# master.net
KiCad netlist of a schematic drawn in Altium Designer
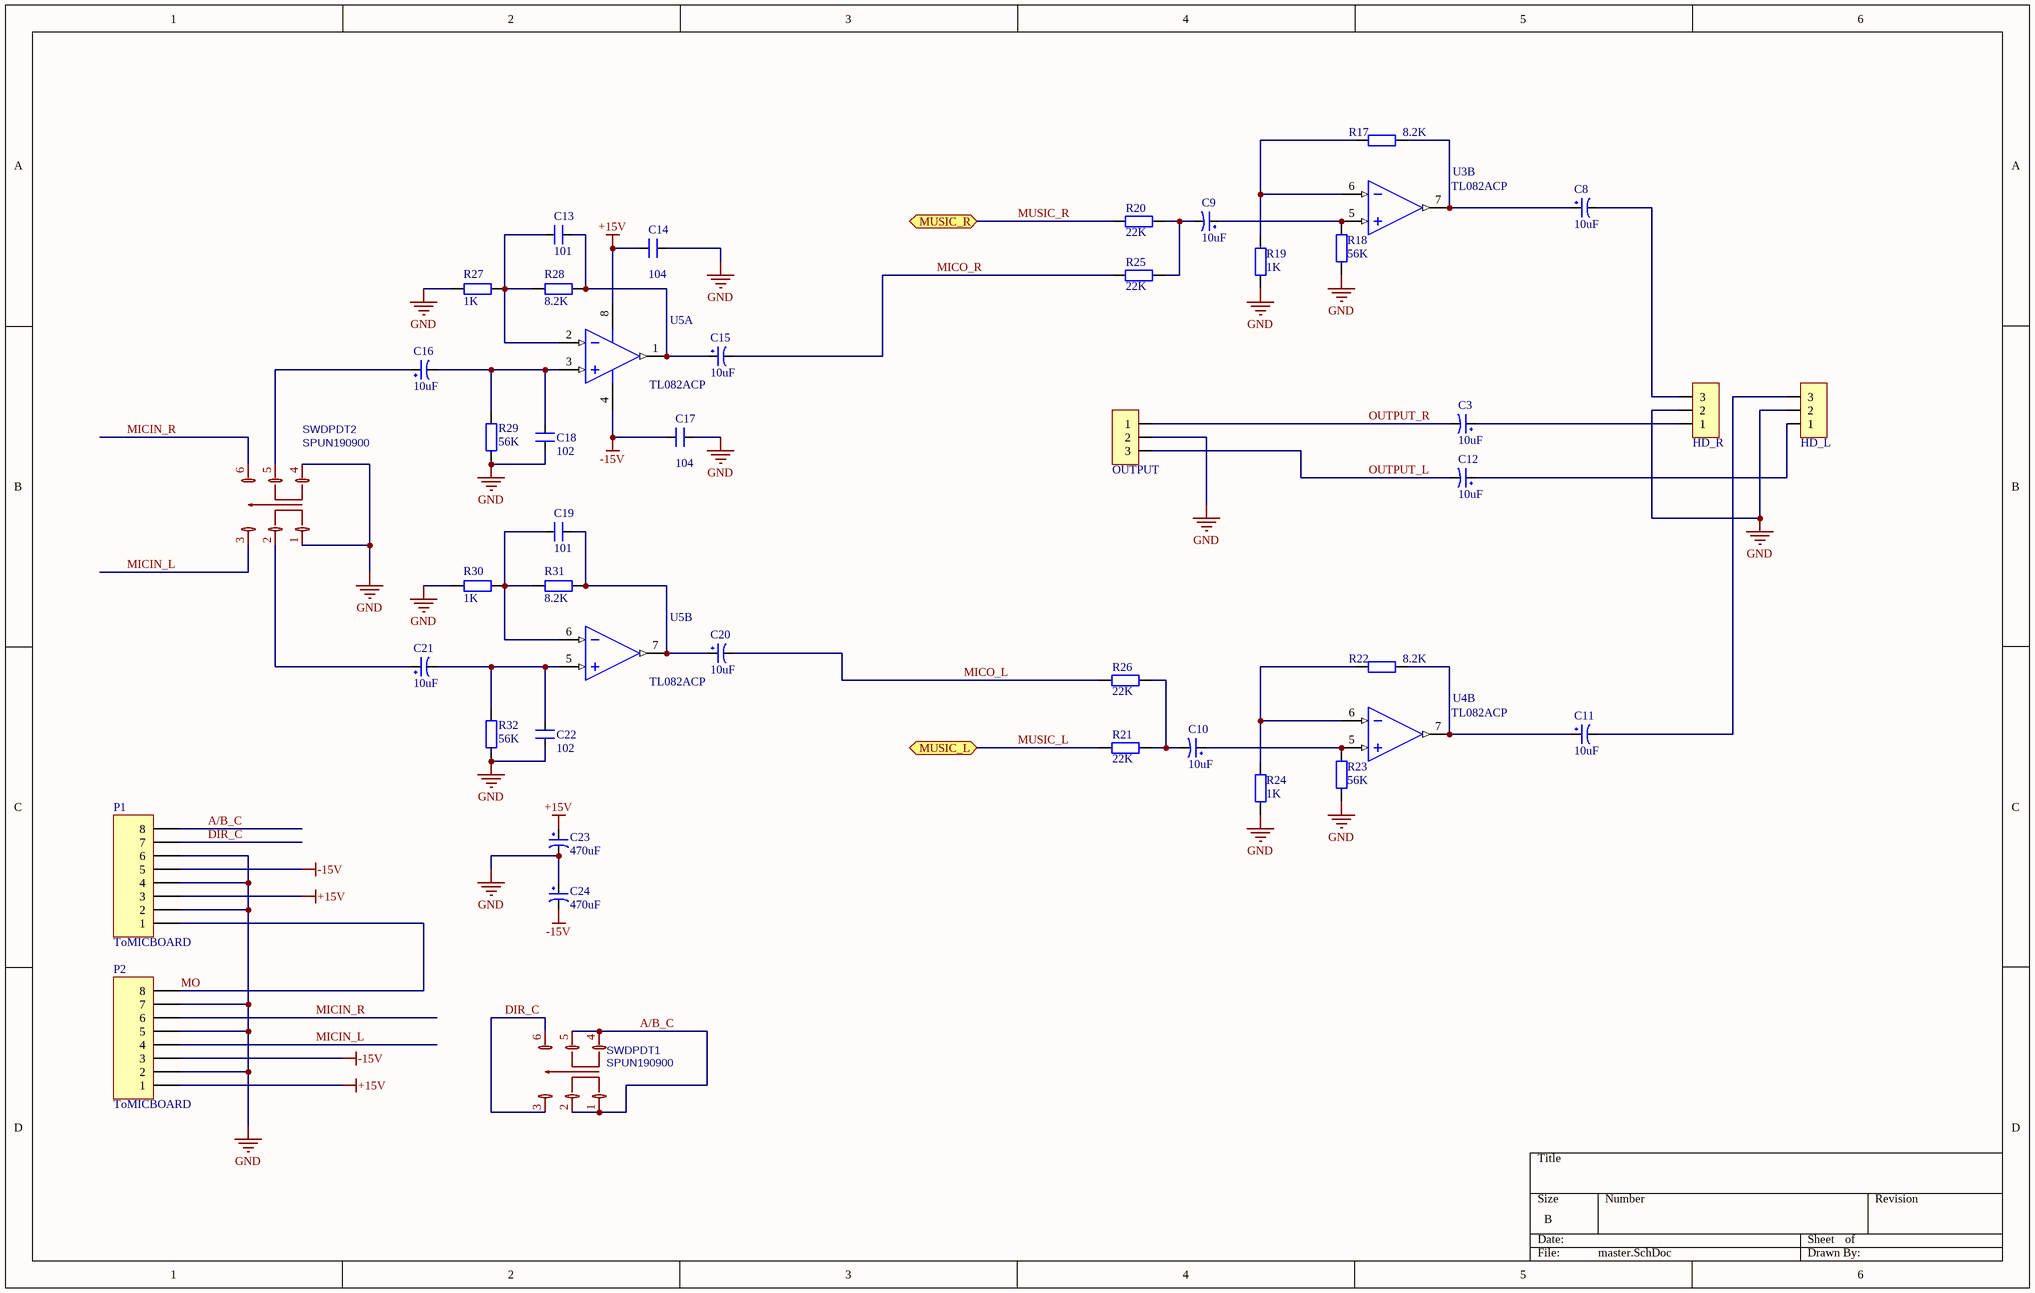
[diagram p0: master.SchDoc]

(export (version "E")
  (design (tool "Eeschema 10.0.6"))
  (components
    (comp (ref "C3")
      (value "10uF")
      (footprint "CAP5x12")
      (description "TU_HOA_4.7uF_100V_MH")
      (libsource (lib "MH_DA_THU_VIEN_16122016") (part "TU_HOA_4.7uF_100V_MH"))
    )
    (comp (ref "C8")
      (value "10uF")
      (footprint "CAP5x12")
      (description "TU_HOA_4.7uF_100V_MH")
      (libsource (lib "MH_DA_THU_VIEN_16122016") (part "TU_HOA_4.7uF_100V_MH"))
    )
    (comp (ref "C9")
      (value "10uF")
      (footprint "CAP5x12")
      (description "TU_HOA_4.7uF_100V_MH")
      (libsource (lib "MH_DA_THU_VIEN_16122016") (part "TU_HOA_4.7uF_100V_MH"))
    )
    (comp (ref "C10")
      (value "10uF")
      (footprint "CAP5x12")
      (description "TU_HOA_4.7uF_100V_MH")
      (libsource (lib "MH_DA_THU_VIEN_16122016") (part "TU_HOA_4.7uF_100V_MH"))
    )
    (comp (ref "C11")
      (value "10uF")
      (footprint "CAP5x12")
      (description "TU_HOA_4.7uF_100V_MH")
      (libsource (lib "MH_DA_THU_VIEN_16122016") (part "TU_HOA_4.7uF_100V_MH"))
    )
    (comp (ref "C12")
      (value "10uF")
      (footprint "CAP5x12")
      (description "TU_HOA_4.7uF_100V_MH")
      (libsource (lib "MH_DA_THU_VIEN_16122016") (part "TU_HOA_4.7uF_100V_MH"))
    )
    (comp (ref "C13")
      (value "101")
      (footprint "TU_GOM(104-->105pF)")
      (libsource (lib "MH_DA_THU_VIEN_16122016") (part "TU_GOM(104 ={gt} 105pF)_MH"))
    )
    (comp (ref "C14")
      (value "104")
      (footprint "TU_GOM(104-->105pF)")
      (libsource (lib "MH_DA_THU_VIEN_16122016") (part "TU_MICA_ 104 100V(2A104J)_MH"))
    )
    (comp (ref "C15")
      (value "10uF")
      (footprint "CAP5x12")
      (description "TU_HOA_4.7uF_100V_MH")
      (libsource (lib "MH_DA_THU_VIEN_16122016") (part "TU_HOA_4.7uF_100V_MH"))
    )
    (comp (ref "C16") (value "10uF") (footprint "CAP5x12") (libsource (lib "") (part "TU_HOA_10uF_16V_MH_1")))
    (comp (ref "C17")
      (value "104")
      (footprint "TU_GOM(104-->105pF)")
      (libsource (lib "MH_DA_THU_VIEN_16122016") (part "TU_MICA_ 104 100V(2A104J)_MH"))
    )
    (comp (ref "C18")
      (value "102")
      (footprint "TU_GOM(104-->105pF)")
      (libsource (lib "MH_DA_THU_VIEN_16122016") (part "TU_GOM(104 ={gt} 105pF)_MH"))
    )
    (comp (ref "C19")
      (value "101")
      (footprint "TU_GOM(104-->105pF)")
      (libsource (lib "MH_DA_THU_VIEN_16122016") (part "TU_GOM(104 ={gt} 105pF)_MH"))
    )
    (comp (ref "C20")
      (value "10uF")
      (footprint "CAP5x12")
      (description "TU_HOA_4.7uF_100V_MH")
      (libsource (lib "MH_DA_THU_VIEN_16122016") (part "TU_HOA_4.7uF_100V_MH"))
    )
    (comp (ref "C21") (value "10uF") (footprint "CAP5x12") (libsource (lib "") (part "TU_HOA_10uF_16V_MH_1")))
    (comp (ref "C22")
      (value "102")
      (footprint "TU_GOM(104-->105pF)")
      (libsource (lib "MH_DA_THU_VIEN_16122016") (part "TU_GOM(104 ={gt} 105pF)_MH"))
    )
    (comp (ref "C23")
      (value "470uF")
      (footprint "TU_HOA(100uF/35V - 470uF/16V)")
      (description "10uF")
      (libsource (lib "MH_DA_THU_VIEN_16122016") (part "TU_HOA_10uF_16V_MH"))
    )
    (comp (ref "C24")
      (value "470uF")
      (footprint "TU_HOA(100uF/35V - 470uF/16V)")
      (description "10uF")
      (libsource (lib "MH_DA_THU_VIEN_16122016") (part "TU_HOA_10uF_16V_MH"))
    )
    (comp (ref "HD_L")
      (value "Header 3_MH")
      (footprint "HEADER 3")
      (description "Header 3P XH2.54 thẳng")
      (libsource (lib "MH_DA_THU_VIEN_16122016") (part "Header 3_MH"))
    )
    (comp (ref "HD_R")
      (value "Header 3_MH")
      (footprint "HEADER 3")
      (description "Header 3P XH2.54 thẳng")
      (libsource (lib "MH_DA_THU_VIEN_16122016") (part "Header 3_MH"))
    )
    (comp (ref "OUTPUT")
      (value "Header 3_MH")
      (footprint "HEADER 3")
      (description "Header 3P XH2.54 thẳng")
      (libsource (lib "") (part "Header 3_MH_1"))
    )
    (comp (ref "P1")
      (value "ToMICBOARD")
      (footprint "HEADER 8")
      (description "Header, 8-Pin")
      (fields (field (name "PUBLISHER") "Altium Limited"))
      (libsource (lib "Miscellaneous Connectors") (part "Header 8"))
    )
    (comp (ref "P2")
      (value "ToMICBOARD")
      (footprint "HEADER 8")
      (description "Header, 8-Pin")
      (fields (field (name "PUBLISHER") "Altium Limited"))
      (libsource (lib "Miscellaneous Connectors") (part "Header 8"))
    )
    (comp (ref "R17")
      (value "8.2K")
      (footprint "TRO_VACH_ 1/4W")
      (description "Resistor")
      (fields (field (name "PUBLISHER") "Altium Limited"))
      (libsource (lib "") (part "TRO_VACH_1/2W_MH_2"))
    )
    (comp (ref "R18")
      (value "56K")
      (footprint "TRO_VACH_ 1/4W")
      (description "Resistor")
      (fields (field (name "PUBLISHER") "Altium Limited"))
      (libsource (lib "MH_DA_THU_VIEN_16122016") (part "TRO_VACH_1/2W_MH"))
    )
    (comp (ref "R19")
      (value "1K")
      (footprint "TRO_VACH_ 1/4W")
      (description "Resistor")
      (fields (field (name "PUBLISHER") "Altium Limited"))
      (libsource (lib "MH_DA_THU_VIEN_16122016") (part "TRO_VACH_1/2W_MH"))
    )
    (comp (ref "R20")
      (value "22K")
      (footprint "TRO_VACH_ 1/4W")
      (description "Resistor")
      (fields (field (name "PUBLISHER") "Altium Limited"))
      (libsource (lib "") (part "TRO_VACH_1/2W_MH_1"))
    )
    (comp (ref "R21")
      (value "22K")
      (footprint "TRO_VACH_ 1/4W")
      (description "Resistor")
      (fields (field (name "PUBLISHER") "Altium Limited"))
      (libsource (lib "") (part "TRO_VACH_1/2W_MH_1"))
    )
    (comp (ref "R22")
      (value "8.2K")
      (footprint "TRO_VACH_ 1/4W")
      (description "Resistor")
      (fields (field (name "PUBLISHER") "Altium Limited"))
      (libsource (lib "") (part "TRO_VACH_1/2W_MH_2"))
    )
    (comp (ref "R23")
      (value "56K")
      (footprint "TRO_VACH_ 1/4W")
      (description "Resistor")
      (fields (field (name "PUBLISHER") "Altium Limited"))
      (libsource (lib "MH_DA_THU_VIEN_16122016") (part "TRO_VACH_1/2W_MH"))
    )
    (comp (ref "R24")
      (value "1K")
      (footprint "TRO_VACH_ 1/4W")
      (description "Resistor")
      (fields (field (name "PUBLISHER") "Altium Limited"))
      (libsource (lib "MH_DA_THU_VIEN_16122016") (part "TRO_VACH_1/2W_MH"))
    )
    (comp (ref "R25")
      (value "22K")
      (footprint "TRO_VACH_ 1/4W")
      (description "Resistor")
      (fields (field (name "PUBLISHER") "Altium Limited"))
      (libsource (lib "") (part "TRO_VACH_1/2W_MH_1"))
    )
    (comp (ref "R26")
      (value "22K")
      (footprint "TRO_VACH_ 1/4W")
      (description "Resistor")
      (fields (field (name "PUBLISHER") "Altium Limited"))
      (libsource (lib "") (part "TRO_VACH_1/2W_MH_1"))
    )
    (comp (ref "R27")
      (value "1K")
      (footprint "TRO_VACH_ 1/4W")
      (libsource (lib "MH_DA_THU_VIEN_16122016") (part "TRO_VACH_1/4W_MH"))
    )
    (comp (ref "R28")
      (value "8.2K")
      (footprint "TRO_VACH_ 1/4W")
      (libsource (lib "MH_DA_THU_VIEN_16122016") (part "TRO_VACH_1/4W_MH"))
    )
    (comp (ref "R29")
      (value "56K")
      (footprint "TRO_VACH_ 1/4W")
      (libsource (lib "MH_DA_THU_VIEN_16122016") (part "TRO_VACH_1/4W_MH"))
    )
    (comp (ref "R30")
      (value "1K")
      (footprint "TRO_VACH_ 1/4W")
      (libsource (lib "MH_DA_THU_VIEN_16122016") (part "TRO_VACH_1/4W_MH"))
    )
    (comp (ref "R31")
      (value "8.2K")
      (footprint "TRO_VACH_ 1/4W")
      (libsource (lib "MH_DA_THU_VIEN_16122016") (part "TRO_VACH_1/4W_MH"))
    )
    (comp (ref "R32")
      (value "56K")
      (footprint "TRO_VACH_ 1/4W")
      (libsource (lib "MH_DA_THU_VIEN_16122016") (part "TRO_VACH_1/4W_MH"))
    )
    (comp (ref "SWDPDT1")
      (value "SPUN190900")
      (footprint "SW-DIP-P42X10")
      (fields (field (name "BOM_SUPPLIER PART") "C278339") (field (name "CONTRIBUTOR") "LCSC"))
      (libsource (lib "Schlib1") (part "SPUN190900"))
    )
    (comp (ref "SWDPDT2")
      (value "SPUN190900")
      (footprint "SW-DIP-P42X10")
      (fields (field (name "BOM_SUPPLIER PART") "C278339") (field (name "CONTRIBUTOR") "LCSC"))
      (libsource (lib "Schlib1") (part "SPUN190900"))
    )
    (comp (ref "U3")
      (value "TL082ACP")
      (footprint "DIP8")
      (description "JFET-Input Operational Amplifier")
      (fields (field (name "PUBLISHER") "Altium Limited"))
      (libsource (lib "Schlib1") (part "TL082ACP"))
    )
    (comp (ref "U4")
      (value "TL082ACP")
      (footprint "DIP8")
      (description "JFET-Input Operational Amplifier")
      (fields (field (name "PUBLISHER") "Altium Limited"))
      (libsource (lib "Schlib1") (part "TL082ACP"))
    )
    (comp (ref "U5")
      (value "TL082ACP")
      (footprint "DIP8")
      (description "JFET-Input Operational Amplifier")
      (fields (field (name "PUBLISHER") "Altium Limited"))
      (libsource (lib "Schlib1") (part "TL082ACP"))
    )
  )
  (nets
    (net (code "1") (name "+15V") (class "Default")
      (node (ref "C14") (pin "1") (pinfunction "1_1") (pintype "passive"))
      (node (ref "C23") (pin "1") (pinfunction "1_1") (pintype "passive"))
      (node (ref "P1") (pin "3") (pinfunction "3_3") (pintype "passive"))
      (node (ref "P2") (pin "1") (pinfunction "1_1") (pintype "passive"))
      (node (ref "U5") (pin "8") (pinfunction "V+_8") (pintype "power_in"))
    )
    (net (code "2") (name "-15V") (class "Default")
      (node (ref "C17") (pin "1") (pinfunction "1_1") (pintype "passive"))
      (node (ref "C24") (pin "2") (pinfunction "2_2") (pintype "passive"))
      (node (ref "P1") (pin "5") (pinfunction "5_5") (pintype "passive"))
      (node (ref "P2") (pin "3") (pinfunction "3_3") (pintype "passive"))
      (node (ref "U5") (pin "4") (pinfunction "V-_4") (pintype "power_in"))
    )
    (net (code "3") (name "/A{slash}B_C") (class "Default")
      (node (ref "P1") (pin "8") (pinfunction "8_8") (pintype "passive"))
      (node (ref "SWDPDT1") (pin "1") (pinfunction "1_1") (pintype "passive"))
      (node (ref "SWDPDT1") (pin "2") (pinfunction "2_2") (pintype "passive"))
      (node (ref "SWDPDT1") (pin "4") (pinfunction "4_4") (pintype "passive"))
      (node (ref "SWDPDT1") (pin "5") (pinfunction "5_5") (pintype "passive"))
    )
    (net (code "4") (name "/DIR_C") (class "Default")
      (node (ref "P1") (pin "7") (pinfunction "7_7") (pintype "passive"))
      (node (ref "SWDPDT1") (pin "3") (pinfunction "3_3") (pintype "passive"))
      (node (ref "SWDPDT1") (pin "6") (pinfunction "6_6") (pintype "passive"))
    )
    (net (code "5") (name "/MICIN_L") (class "Default")
      (node (ref "P2") (pin "4") (pinfunction "4_4") (pintype "passive"))
      (node (ref "SWDPDT2") (pin "3") (pinfunction "3_3") (pintype "passive"))
    )
    (net (code "6") (name "/MICIN_R") (class "Default")
      (node (ref "P2") (pin "6") (pinfunction "6_6") (pintype "passive"))
      (node (ref "SWDPDT2") (pin "6") (pinfunction "6_6") (pintype "passive"))
    )
    (net (code "7") (name "/MICO_L") (class "Default")
      (node (ref "C20") (pin "2") (pinfunction "2_2") (pintype "passive"))
      (node (ref "R26") (pin "1") (pinfunction "1_1") (pintype "passive"))
    )
    (net (code "8") (name "/MICO_R") (class "Default")
      (node (ref "C15") (pin "2") (pinfunction "2_2") (pintype "passive"))
      (node (ref "R25") (pin "1") (pinfunction "1_1") (pintype "passive"))
    )
    (net (code "9") (name "/MO") (class "Default")
      (node (ref "P1") (pin "1") (pinfunction "1_1") (pintype "passive"))
      (node (ref "P2") (pin "8") (pinfunction "8_8") (pintype "passive"))
    )
    (net (code "10") (name "/MUSIC_L") (class "Default")
      (node (ref "R21") (pin "1") (pinfunction "1_1") (pintype "passive"))
    )
    (net (code "11") (name "/MUSIC_R") (class "Default")
      (node (ref "R20") (pin "1") (pinfunction "1_1") (pintype "passive"))
    )
    (net (code "12") (name "/OUTPUT_L") (class "Default")
      (node (ref "C12") (pin "2") (pinfunction "2_2") (pintype "passive"))
      (node (ref "OUTPUT") (pin "3") (pinfunction "3_3") (pintype "passive"))
    )
    (net (code "13") (name "/OUTPUT_R") (class "Default")
      (node (ref "C3") (pin "2") (pinfunction "2_2") (pintype "passive"))
      (node (ref "OUTPUT") (pin "1") (pinfunction "1_1") (pintype "passive"))
    )
    (net (code "14") (name "GND") (class "Default")
      (node (ref "C14") (pin "2") (pinfunction "2_2") (pintype "passive"))
      (node (ref "C17") (pin "2") (pinfunction "2_2") (pintype "passive"))
      (node (ref "C18") (pin "1") (pinfunction "1_1") (pintype "passive"))
      (node (ref "C22") (pin "1") (pinfunction "1_1") (pintype "passive"))
      (node (ref "C23") (pin "2") (pinfunction "2_2") (pintype "passive"))
      (node (ref "C24") (pin "1") (pinfunction "1_1") (pintype "passive"))
      (node (ref "HD_L") (pin "2") (pinfunction "2_2") (pintype "passive"))
      (node (ref "HD_R") (pin "2") (pinfunction "2_2") (pintype "passive"))
      (node (ref "OUTPUT") (pin "2") (pinfunction "2_2") (pintype "passive"))
      (node (ref "P1") (pin "2") (pinfunction "2_2") (pintype "passive"))
      (node (ref "P1") (pin "4") (pinfunction "4_4") (pintype "passive"))
      (node (ref "P1") (pin "6") (pinfunction "6_6") (pintype "passive"))
      (node (ref "P2") (pin "2") (pinfunction "2_2") (pintype "passive"))
      (node (ref "P2") (pin "5") (pinfunction "5_5") (pintype "passive"))
      (node (ref "P2") (pin "7") (pinfunction "7_7") (pintype "passive"))
      (node (ref "R18") (pin "2") (pinfunction "2_2") (pintype "passive"))
      (node (ref "R19") (pin "2") (pinfunction "2_2") (pintype "passive"))
      (node (ref "R23") (pin "2") (pinfunction "2_2") (pintype "passive"))
      (node (ref "R24") (pin "2") (pinfunction "2_2") (pintype "passive"))
      (node (ref "R27") (pin "1") (pinfunction "1_1") (pintype "passive"))
      (node (ref "R29") (pin "1") (pinfunction "1_1") (pintype "passive"))
      (node (ref "R30") (pin "1") (pinfunction "1_1") (pintype "passive"))
      (node (ref "R32") (pin "1") (pinfunction "1_1") (pintype "passive"))
      (node (ref "SWDPDT2") (pin "1") (pinfunction "1_1") (pintype "passive"))
      (node (ref "SWDPDT2") (pin "4") (pinfunction "4_4") (pintype "passive"))
    )
    (net (code "15") (name "Net-(C3-Pad1)") (class "Default")
      (node (ref "C3") (pin "1") (pinfunction "1_1") (pintype "passive"))
      (node (ref "HD_R") (pin "1") (pinfunction "1_1") (pintype "passive"))
    )
    (net (code "16") (name "Net-(C8-Pad2)") (class "Default")
      (node (ref "C8") (pin "2") (pinfunction "2_2") (pintype "passive"))
      (node (ref "HD_R") (pin "3") (pinfunction "3_3") (pintype "passive"))
    )
    (net (code "17") (name "Net-(C9-Pad2)") (class "Default")
      (node (ref "C9") (pin "2") (pinfunction "2_2") (pintype "passive"))
      (node (ref "R20") (pin "2") (pinfunction "2_2") (pintype "passive"))
      (node (ref "R25") (pin "2") (pinfunction "2_2") (pintype "passive"))
    )
    (net (code "18") (name "Net-(C10-Pad2)") (class "Default")
      (node (ref "C10") (pin "2") (pinfunction "2_2") (pintype "passive"))
      (node (ref "R21") (pin "2") (pinfunction "2_2") (pintype "passive"))
      (node (ref "R26") (pin "2") (pinfunction "2_2") (pintype "passive"))
    )
    (net (code "19") (name "Net-(C11-Pad2)") (class "Default")
      (node (ref "C11") (pin "2") (pinfunction "2_2") (pintype "passive"))
      (node (ref "HD_L") (pin "3") (pinfunction "3_3") (pintype "passive"))
    )
    (net (code "20") (name "Net-(C12-Pad1)") (class "Default")
      (node (ref "C12") (pin "1") (pinfunction "1_1") (pintype "passive"))
      (node (ref "HD_L") (pin "1") (pinfunction "1_1") (pintype "passive"))
    )
    (net (code "21") (name "Net-(C16-Pad1)") (class "Default")
      (node (ref "C16") (pin "1") (pinfunction "1_1") (pintype "passive"))
      (node (ref "SWDPDT2") (pin "5") (pinfunction "5_5") (pintype "passive"))
    )
    (net (code "22") (name "Net-(C21-Pad1)") (class "Default")
      (node (ref "C21") (pin "1") (pinfunction "1_1") (pintype "passive"))
      (node (ref "SWDPDT2") (pin "2") (pinfunction "2_2") (pintype "passive"))
    )
    (net (code "23") (name "Net-(U3B-IN+)") (class "Default")
      (node (ref "C9") (pin "1") (pinfunction "1_1") (pintype "passive"))
      (node (ref "R18") (pin "1") (pinfunction "1_1") (pintype "passive"))
      (node (ref "U3") (pin "5") (pinfunction "IN+_5") (pintype "input"))
    )
    (net (code "24") (name "Net-(U3B-IN-)") (class "Default")
      (node (ref "R17") (pin "2") (pinfunction "2_2") (pintype "passive"))
      (node (ref "R19") (pin "1") (pinfunction "1_1") (pintype "passive"))
      (node (ref "U3") (pin "6") (pinfunction "IN-_6") (pintype "input"))
    )
    (net (code "25") (name "Net-(U3B-OUT)") (class "Default")
      (node (ref "C8") (pin "1") (pinfunction "1_1") (pintype "passive"))
      (node (ref "R17") (pin "1") (pinfunction "1_1") (pintype "passive"))
      (node (ref "U3") (pin "7") (pinfunction "OUT_7") (pintype "output"))
    )
    (net (code "26") (name "Net-(U4B-IN+)") (class "Default")
      (node (ref "C10") (pin "1") (pinfunction "1_1") (pintype "passive"))
      (node (ref "R23") (pin "1") (pinfunction "1_1") (pintype "passive"))
      (node (ref "U4") (pin "5") (pinfunction "IN+_5") (pintype "input"))
    )
    (net (code "27") (name "Net-(U4B-IN-)") (class "Default")
      (node (ref "R22") (pin "2") (pinfunction "2_2") (pintype "passive"))
      (node (ref "R24") (pin "1") (pinfunction "1_1") (pintype "passive"))
      (node (ref "U4") (pin "6") (pinfunction "IN-_6") (pintype "input"))
    )
    (net (code "28") (name "Net-(U4B-OUT)") (class "Default")
      (node (ref "C11") (pin "1") (pinfunction "1_1") (pintype "passive"))
      (node (ref "R22") (pin "1") (pinfunction "1_1") (pintype "passive"))
      (node (ref "U4") (pin "7") (pinfunction "OUT_7") (pintype "output"))
    )
    (net (code "29") (name "Net-(U5A-IN+)") (class "Default")
      (node (ref "C16") (pin "2") (pinfunction "2_2") (pintype "passive"))
      (node (ref "C18") (pin "2") (pinfunction "2_2") (pintype "passive"))
      (node (ref "R29") (pin "2") (pinfunction "2_2") (pintype "passive"))
      (node (ref "U5") (pin "3") (pinfunction "IN+_3") (pintype "input"))
    )
    (net (code "30") (name "Net-(U5A-IN-)") (class "Default")
      (node (ref "C13") (pin "2") (pinfunction "2_2") (pintype "passive"))
      (node (ref "R27") (pin "2") (pinfunction "2_2") (pintype "passive"))
      (node (ref "R28") (pin "2") (pinfunction "2_2") (pintype "passive"))
      (node (ref "U5") (pin "2") (pinfunction "IN-_2") (pintype "input"))
    )
    (net (code "31") (name "Net-(U5A-OUT)") (class "Default")
      (node (ref "C13") (pin "1") (pinfunction "1_1") (pintype "passive"))
      (node (ref "C15") (pin "1") (pinfunction "1_1") (pintype "passive"))
      (node (ref "R28") (pin "1") (pinfunction "1_1") (pintype "passive"))
      (node (ref "U5") (pin "1") (pinfunction "OUT_1") (pintype "output"))
    )
    (net (code "32") (name "Net-(U5B-IN+)") (class "Default")
      (node (ref "C21") (pin "2") (pinfunction "2_2") (pintype "passive"))
      (node (ref "C22") (pin "2") (pinfunction "2_2") (pintype "passive"))
      (node (ref "R32") (pin "2") (pinfunction "2_2") (pintype "passive"))
      (node (ref "U5") (pin "5") (pinfunction "IN+_5") (pintype "input"))
    )
    (net (code "33") (name "Net-(U5B-IN-)") (class "Default")
      (node (ref "C19") (pin "2") (pinfunction "2_2") (pintype "passive"))
      (node (ref "R30") (pin "2") (pinfunction "2_2") (pintype "passive"))
      (node (ref "R31") (pin "2") (pinfunction "2_2") (pintype "passive"))
      (node (ref "U5") (pin "6") (pinfunction "IN-_6") (pintype "input"))
    )
    (net (code "34") (name "Net-(U5B-OUT)") (class "Default")
      (node (ref "C19") (pin "1") (pinfunction "1_1") (pintype "passive"))
      (node (ref "C20") (pin "1") (pinfunction "1_1") (pintype "passive"))
      (node (ref "R31") (pin "1") (pinfunction "1_1") (pintype "passive"))
      (node (ref "U5") (pin "7") (pinfunction "OUT_7") (pintype "output"))
    )
  )
)
